# colorTemp.net
KiCad netlist of a schematic drawn in EAGLE
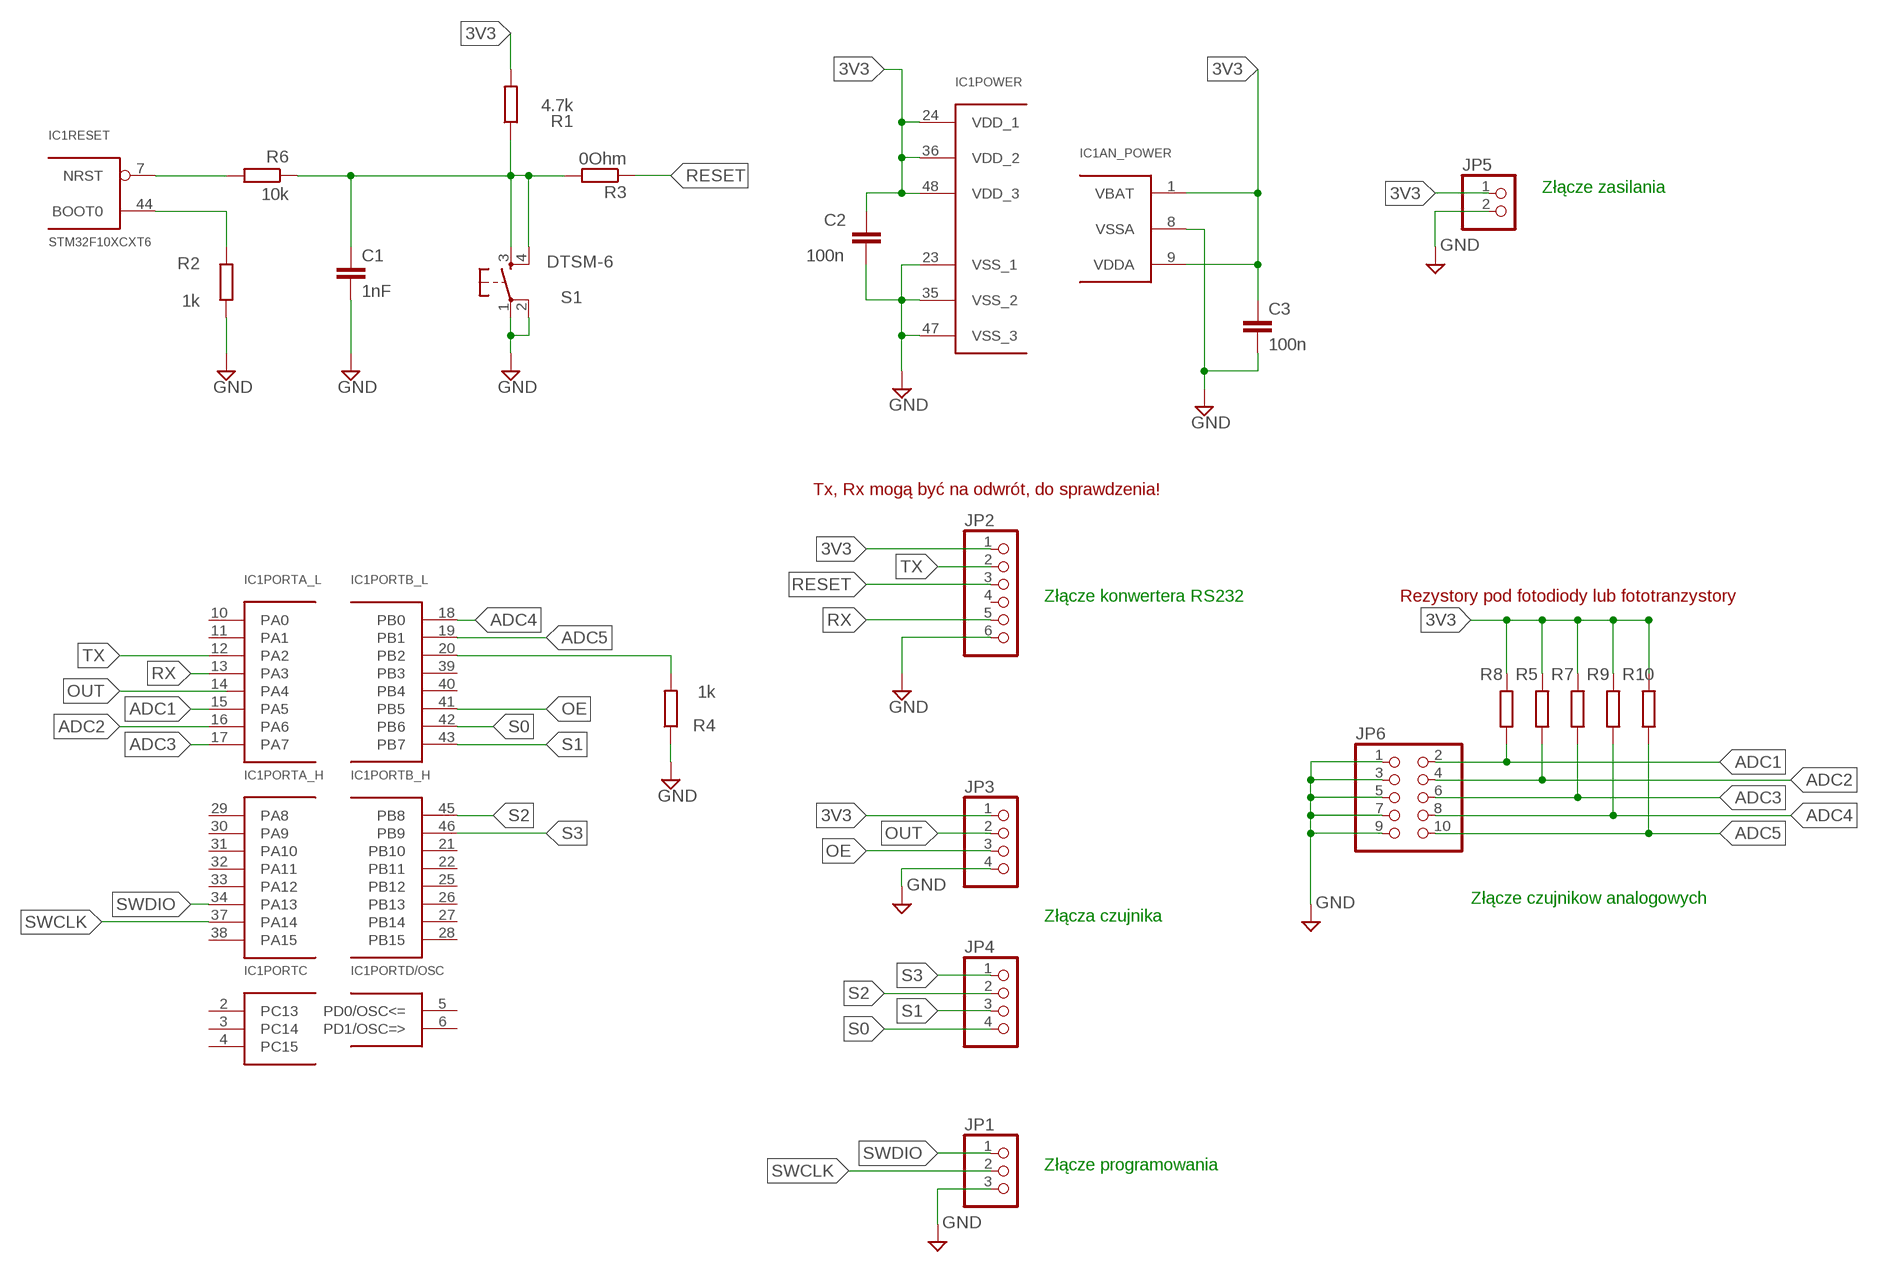
[diagram p0: schematic, sheet 1]

(export (version "E")
  (design (tool "Eeschema 10.0.6"))
  (components
    (comp (ref "C1")
      (value "1nF")
      (footprint "eagle-import:C0402")
      (libsource (lib "eagle-import") (part "C-EUC0402"))
    )
    (comp (ref "C2")
      (value "100n")
      (footprint "eagle-import:C0402")
      (libsource (lib "eagle-import") (part "C-EUC0402"))
    )
    (comp (ref "C3")
      (value "100n")
      (footprint "eagle-import:C0402")
      (libsource (lib "eagle-import") (part "C-EUC0402"))
    )
    (comp (ref "IC1")
      (value "STM32F10XCXT6")
      (footprint "eagle-import:TQFP48")
      (libsource (lib "eagle-import") (part "STM32F10XCXT6"))
    )
    (comp (ref "JP1")
      (value "PINHD-1X3")
      (footprint "eagle-import:1X03")
      (libsource (lib "eagle-import") (part "PINHD-1X3"))
    )
    (comp (ref "JP2")
      (value "PINHD-1X6/90")
      (footprint "eagle-import:1X06_90")
      (libsource (lib "eagle-import") (part "PINHD-1X6/90"))
    )
    (comp (ref "JP3")
      (value "PINHD-1X4")
      (footprint "eagle-import:1X04")
      (libsource (lib "eagle-import") (part "PINHD-1X4"))
    )
    (comp (ref "JP4")
      (value "PINHD-1X4")
      (footprint "eagle-import:1X04")
      (libsource (lib "eagle-import") (part "PINHD-1X4"))
    )
    (comp (ref "JP5")
      (value "PINHD-1X2")
      (footprint "eagle-import:1X02")
      (libsource (lib "eagle-import") (part "PINHD-1X2"))
    )
    (comp (ref "JP6")
      (value "PINHD-2X5")
      (footprint "eagle-import:2X05")
      (libsource (lib "eagle-import") (part "PINHD-2X5"))
    )
    (comp (ref "R1")
      (value "4.7k")
      (footprint "eagle-import:R0402")
      (libsource (lib "eagle-import") (part "R-EU_R0402"))
    )
    (comp (ref "R2")
      (value "1k")
      (footprint "eagle-import:R0402")
      (libsource (lib "eagle-import") (part "R-EU_R0402"))
    )
    (comp (ref "R3")
      (value "0Ohm")
      (footprint "eagle-import:R0402")
      (libsource (lib "eagle-import") (part "R-EU_R0402"))
    )
    (comp (ref "R4")
      (value "1k")
      (footprint "eagle-import:R0402")
      (libsource (lib "eagle-import") (part "R-EU_R0402"))
    )
    (comp (ref "R5")
      (value "R-EU_R0402")
      (footprint "eagle-import:R0402")
      (libsource (lib "eagle-import") (part "R-EU_R0402"))
    )
    (comp (ref "R6")
      (value "10k")
      (footprint "eagle-import:R0402")
      (libsource (lib "eagle-import") (part "R-EU_R0402"))
    )
    (comp (ref "R7")
      (value "R-EU_R0402")
      (footprint "eagle-import:R0402")
      (libsource (lib "eagle-import") (part "R-EU_R0402"))
    )
    (comp (ref "R8")
      (value "R-EU_R0402")
      (footprint "eagle-import:R0402")
      (libsource (lib "eagle-import") (part "R-EU_R0402"))
    )
    (comp (ref "R9")
      (value "R-EU_R0402")
      (footprint "eagle-import:R0402")
      (libsource (lib "eagle-import") (part "R-EU_R0402"))
    )
    (comp (ref "R10")
      (value "R-EU_R0402")
      (footprint "eagle-import:R0402")
      (libsource (lib "eagle-import") (part "R-EU_R0402"))
    )
    (comp (ref "S1")
      (value "DTSM-6")
      (footprint "eagle-import:DTSM-6")
      (libsource (lib "eagle-import") (part "DTSM-6"))
    )
  )
  (nets
    (net (code "1") (name "3V3") (class "Default")
      (node (ref "C2") (pin "1") (pinfunction "1_1") (pintype "passive"))
      (node (ref "C3") (pin "1") (pinfunction "1_1") (pintype "passive"))
      (node (ref "IC1") (pin "1") (pinfunction "VBAT_1") (pintype "power_in"))
      (node (ref "IC1") (pin "24") (pinfunction "VDD_1_24") (pintype "power_in"))
      (node (ref "IC1") (pin "36") (pinfunction "VDD_2_36") (pintype "power_in"))
      (node (ref "IC1") (pin "48") (pinfunction "VDD_3_48") (pintype "power_in"))
      (node (ref "IC1") (pin "9") (pinfunction "VDDA_9") (pintype "power_in"))
      (node (ref "JP2") (pin "1") (pinfunction "1_1") (pintype "passive"))
      (node (ref "JP3") (pin "1") (pinfunction "1_1") (pintype "passive"))
      (node (ref "JP5") (pin "1") (pinfunction "1_1") (pintype "passive"))
      (node (ref "R1") (pin "2") (pinfunction "2_2") (pintype "passive"))
      (node (ref "R10") (pin "1") (pinfunction "1_1") (pintype "passive"))
      (node (ref "R5") (pin "1") (pinfunction "1_1") (pintype "passive"))
      (node (ref "R7") (pin "1") (pinfunction "1_1") (pintype "passive"))
      (node (ref "R8") (pin "1") (pinfunction "1_1") (pintype "passive"))
      (node (ref "R9") (pin "1") (pinfunction "1_1") (pintype "passive"))
    )
    (net (code "2") (name "ADC1") (class "Default")
      (node (ref "IC1") (pin "15") (pinfunction "PA5_15") (pintype "bidirectional"))
      (node (ref "JP6") (pin "2") (pinfunction "2_2") (pintype "passive"))
      (node (ref "R8") (pin "2") (pinfunction "2_2") (pintype "passive"))
    )
    (net (code "3") (name "ADC2") (class "Default")
      (node (ref "IC1") (pin "16") (pinfunction "PA6_16") (pintype "bidirectional"))
      (node (ref "JP6") (pin "4") (pinfunction "4_4") (pintype "passive"))
      (node (ref "R5") (pin "2") (pinfunction "2_2") (pintype "passive"))
    )
    (net (code "4") (name "ADC3") (class "Default")
      (node (ref "IC1") (pin "17") (pinfunction "PA7_17") (pintype "bidirectional"))
      (node (ref "JP6") (pin "6") (pinfunction "6_6") (pintype "passive"))
      (node (ref "R7") (pin "2") (pinfunction "2_2") (pintype "passive"))
    )
    (net (code "5") (name "ADC4") (class "Default")
      (node (ref "IC1") (pin "18") (pinfunction "PB0_18") (pintype "bidirectional"))
      (node (ref "JP6") (pin "8") (pinfunction "8_8") (pintype "passive"))
      (node (ref "R9") (pin "2") (pinfunction "2_2") (pintype "passive"))
    )
    (net (code "6") (name "ADC5") (class "Default")
      (node (ref "IC1") (pin "19") (pinfunction "PB1_19") (pintype "bidirectional"))
      (node (ref "JP6") (pin "10") (pinfunction "10_10") (pintype "passive"))
      (node (ref "R10") (pin "2") (pinfunction "2_2") (pintype "passive"))
    )
    (net (code "7") (name "GND") (class "Default")
      (node (ref "C1") (pin "2") (pinfunction "2_2") (pintype "passive"))
      (node (ref "C2") (pin "2") (pinfunction "2_2") (pintype "passive"))
      (node (ref "C3") (pin "2") (pinfunction "2_2") (pintype "passive"))
      (node (ref "IC1") (pin "23") (pinfunction "VSS_1_23") (pintype "power_in"))
      (node (ref "IC1") (pin "35") (pinfunction "VSS_2_35") (pintype "power_in"))
      (node (ref "IC1") (pin "47") (pinfunction "VSS_3_47") (pintype "power_in"))
      (node (ref "IC1") (pin "8") (pinfunction "VSSA_8") (pintype "power_in"))
      (node (ref "JP1") (pin "3") (pinfunction "3_3") (pintype "passive"))
      (node (ref "JP2") (pin "6") (pinfunction "6_6") (pintype "passive"))
      (node (ref "JP3") (pin "4") (pinfunction "4_4") (pintype "passive"))
      (node (ref "JP5") (pin "2") (pinfunction "2_2") (pintype "passive"))
      (node (ref "JP6") (pin "1") (pinfunction "1_1") (pintype "passive"))
      (node (ref "JP6") (pin "3") (pinfunction "3_3") (pintype "passive"))
      (node (ref "JP6") (pin "5") (pinfunction "5_5") (pintype "passive"))
      (node (ref "JP6") (pin "7") (pinfunction "7_7") (pintype "passive"))
      (node (ref "JP6") (pin "9") (pinfunction "9_9") (pintype "passive"))
      (node (ref "R2") (pin "1") (pinfunction "1_1") (pintype "passive"))
      (node (ref "R4") (pin "1") (pinfunction "1_1") (pintype "passive"))
      (node (ref "S1") (pin "1") (pinfunction "1_1") (pintype "passive"))
      (node (ref "S1") (pin "2") (pinfunction "2_2") (pintype "passive"))
    )
    (net (code "8") (name "Net-(C1-Pad1)") (class "Default")
      (node (ref "C1") (pin "1") (pinfunction "1_1") (pintype "passive"))
      (node (ref "R1") (pin "1") (pinfunction "1_1") (pintype "passive"))
      (node (ref "R3") (pin "2") (pinfunction "2_2") (pintype "passive"))
      (node (ref "R6") (pin "1") (pinfunction "1_1") (pintype "passive"))
      (node (ref "S1") (pin "3") (pinfunction "3_3") (pintype "passive"))
      (node (ref "S1") (pin "4") (pinfunction "4_4") (pintype "passive"))
    )
    (net (code "9") (name "Net-(IC1E-PB2)") (class "Default")
      (node (ref "IC1") (pin "20") (pinfunction "PB2_20") (pintype "bidirectional"))
      (node (ref "R4") (pin "2") (pinfunction "2_2") (pintype "passive"))
    )
    (net (code "10") (name "Net-(IC1I-BOOT0)") (class "Default")
      (node (ref "IC1") (pin "44") (pinfunction "BOOT0_44") (pintype "input"))
      (node (ref "R2") (pin "2") (pinfunction "2_2") (pintype "passive"))
    )
    (net (code "11") (name "Net-(IC1I-NRST)") (class "Default")
      (node (ref "IC1") (pin "7") (pinfunction "NRST_7") (pintype "input"))
      (node (ref "R6") (pin "2") (pinfunction "2_2") (pintype "passive"))
    )
    (net (code "12") (name "OE") (class "Default")
      (node (ref "IC1") (pin "41") (pinfunction "PB5_41") (pintype "bidirectional"))
      (node (ref "JP3") (pin "3") (pinfunction "3_3") (pintype "passive"))
    )
    (net (code "13") (name "OUT") (class "Default")
      (node (ref "IC1") (pin "14") (pinfunction "PA4_14") (pintype "bidirectional"))
      (node (ref "JP3") (pin "2") (pinfunction "2_2") (pintype "passive"))
    )
    (net (code "14") (name "RESET") (class "Default")
      (node (ref "JP2") (pin "3") (pinfunction "3_3") (pintype "passive"))
      (node (ref "R3") (pin "1") (pinfunction "1_1") (pintype "passive"))
    )
    (net (code "15") (name "RX") (class "Default")
      (node (ref "IC1") (pin "13") (pinfunction "PA3_13") (pintype "bidirectional"))
      (node (ref "JP2") (pin "5") (pinfunction "5_5") (pintype "passive"))
    )
    (net (code "16") (name "S0") (class "Default")
      (node (ref "IC1") (pin "42") (pinfunction "PB6_42") (pintype "bidirectional"))
      (node (ref "JP4") (pin "4") (pinfunction "4_4") (pintype "passive"))
    )
    (net (code "17") (name "S1") (class "Default")
      (node (ref "IC1") (pin "43") (pinfunction "PB7_43") (pintype "bidirectional"))
      (node (ref "JP4") (pin "3") (pinfunction "3_3") (pintype "passive"))
    )
    (net (code "18") (name "S2") (class "Default")
      (node (ref "IC1") (pin "45") (pinfunction "PB8_45") (pintype "bidirectional"))
      (node (ref "JP4") (pin "2") (pinfunction "2_2") (pintype "passive"))
    )
    (net (code "19") (name "S3") (class "Default")
      (node (ref "IC1") (pin "46") (pinfunction "PB9_46") (pintype "bidirectional"))
      (node (ref "JP4") (pin "1") (pinfunction "1_1") (pintype "passive"))
    )
    (net (code "20") (name "SWCLK") (class "Default")
      (node (ref "IC1") (pin "37") (pinfunction "PA14_37") (pintype "bidirectional"))
      (node (ref "JP1") (pin "2") (pinfunction "2_2") (pintype "passive"))
    )
    (net (code "21") (name "SWDIO") (class "Default")
      (node (ref "IC1") (pin "34") (pinfunction "PA13_34") (pintype "bidirectional"))
      (node (ref "JP1") (pin "1") (pinfunction "1_1") (pintype "passive"))
    )
    (net (code "22") (name "TX") (class "Default")
      (node (ref "IC1") (pin "12") (pinfunction "PA2_12") (pintype "bidirectional"))
      (node (ref "JP2") (pin "2") (pinfunction "2_2") (pintype "passive"))
    )
    (net (code "23") (name "unconnected-(IC1B-PA8-Pad29)") (class "Default")
      (node (ref "IC1") (pin "29") (pinfunction "PA8_29") (pintype "bidirectional"))
    )
    (net (code "24") (name "unconnected-(IC1B-PA9-Pad30)") (class "Default")
      (node (ref "IC1") (pin "30") (pinfunction "PA9_30") (pintype "bidirectional"))
    )
    (net (code "25") (name "unconnected-(IC1B-PA10-Pad31)") (class "Default")
      (node (ref "IC1") (pin "31") (pinfunction "PA10_31") (pintype "bidirectional"))
    )
    (net (code "26") (name "unconnected-(IC1B-PA11-Pad32)") (class "Default")
      (node (ref "IC1") (pin "32") (pinfunction "PA11_32") (pintype "bidirectional"))
    )
    (net (code "27") (name "unconnected-(IC1B-PA12-Pad33)") (class "Default")
      (node (ref "IC1") (pin "33") (pinfunction "PA12_33") (pintype "bidirectional"))
    )
    (net (code "28") (name "unconnected-(IC1B-PA15-Pad38)") (class "Default")
      (node (ref "IC1") (pin "38") (pinfunction "PA15_38") (pintype "bidirectional"))
    )
    (net (code "29") (name "unconnected-(IC1C-PA0-Pad10)") (class "Default")
      (node (ref "IC1") (pin "10") (pinfunction "PA0_10") (pintype "bidirectional"))
    )
    (net (code "30") (name "unconnected-(IC1C-PA1-Pad11)") (class "Default")
      (node (ref "IC1") (pin "11") (pinfunction "PA1_11") (pintype "bidirectional"))
    )
    (net (code "31") (name "unconnected-(IC1D-PB10-Pad21)") (class "Default")
      (node (ref "IC1") (pin "21") (pinfunction "PB10_21") (pintype "bidirectional"))
    )
    (net (code "32") (name "unconnected-(IC1D-PB11-Pad22)") (class "Default")
      (node (ref "IC1") (pin "22") (pinfunction "PB11_22") (pintype "bidirectional"))
    )
    (net (code "33") (name "unconnected-(IC1D-PB12-Pad25)") (class "Default")
      (node (ref "IC1") (pin "25") (pinfunction "PB12_25") (pintype "bidirectional"))
    )
    (net (code "34") (name "unconnected-(IC1D-PB13-Pad26)") (class "Default")
      (node (ref "IC1") (pin "26") (pinfunction "PB13_26") (pintype "bidirectional"))
    )
    (net (code "35") (name "unconnected-(IC1D-PB14-Pad27)") (class "Default")
      (node (ref "IC1") (pin "27") (pinfunction "PB14_27") (pintype "bidirectional"))
    )
    (net (code "36") (name "unconnected-(IC1D-PB15-Pad28)") (class "Default")
      (node (ref "IC1") (pin "28") (pinfunction "PB15_28") (pintype "bidirectional"))
    )
    (net (code "37") (name "unconnected-(IC1E-PB3-Pad39)") (class "Default")
      (node (ref "IC1") (pin "39") (pinfunction "PB3_39") (pintype "bidirectional"))
    )
    (net (code "38") (name "unconnected-(IC1E-PB4-Pad40)") (class "Default")
      (node (ref "IC1") (pin "40") (pinfunction "PB4_40") (pintype "bidirectional"))
    )
    (net (code "39") (name "unconnected-(IC1F-PC13-Pad2)") (class "Default")
      (node (ref "IC1") (pin "2") (pinfunction "PC13_2") (pintype "bidirectional"))
    )
    (net (code "40") (name "unconnected-(IC1F-PC14-Pad3)") (class "Default")
      (node (ref "IC1") (pin "3") (pinfunction "PC14_3") (pintype "bidirectional"))
    )
    (net (code "41") (name "unconnected-(IC1F-PC15-Pad4)") (class "Default")
      (node (ref "IC1") (pin "4") (pinfunction "PC15_4") (pintype "bidirectional"))
    )
    (net (code "42") (name "unconnected-(IC1G-PD0{slash}OSC<=-Pad5)") (class "Default")
      (node (ref "IC1") (pin "5") (pinfunction "PD0/OSC<=_5") (pintype "bidirectional"))
    )
    (net (code "43") (name "unconnected-(IC1G-PD1{slash}OSC=>-Pad6)") (class "Default")
      (node (ref "IC1") (pin "6") (pinfunction "PD1/OSC=>_6") (pintype "bidirectional"))
    )
    (net (code "44") (name "unconnected-(JP2-Pad4)") (class "Default")
      (node (ref "JP2") (pin "4") (pinfunction "4_4") (pintype "passive"))
    )
  )
)
